# Pwr.net
KiCad netlist of a schematic drawn in Altium Designer
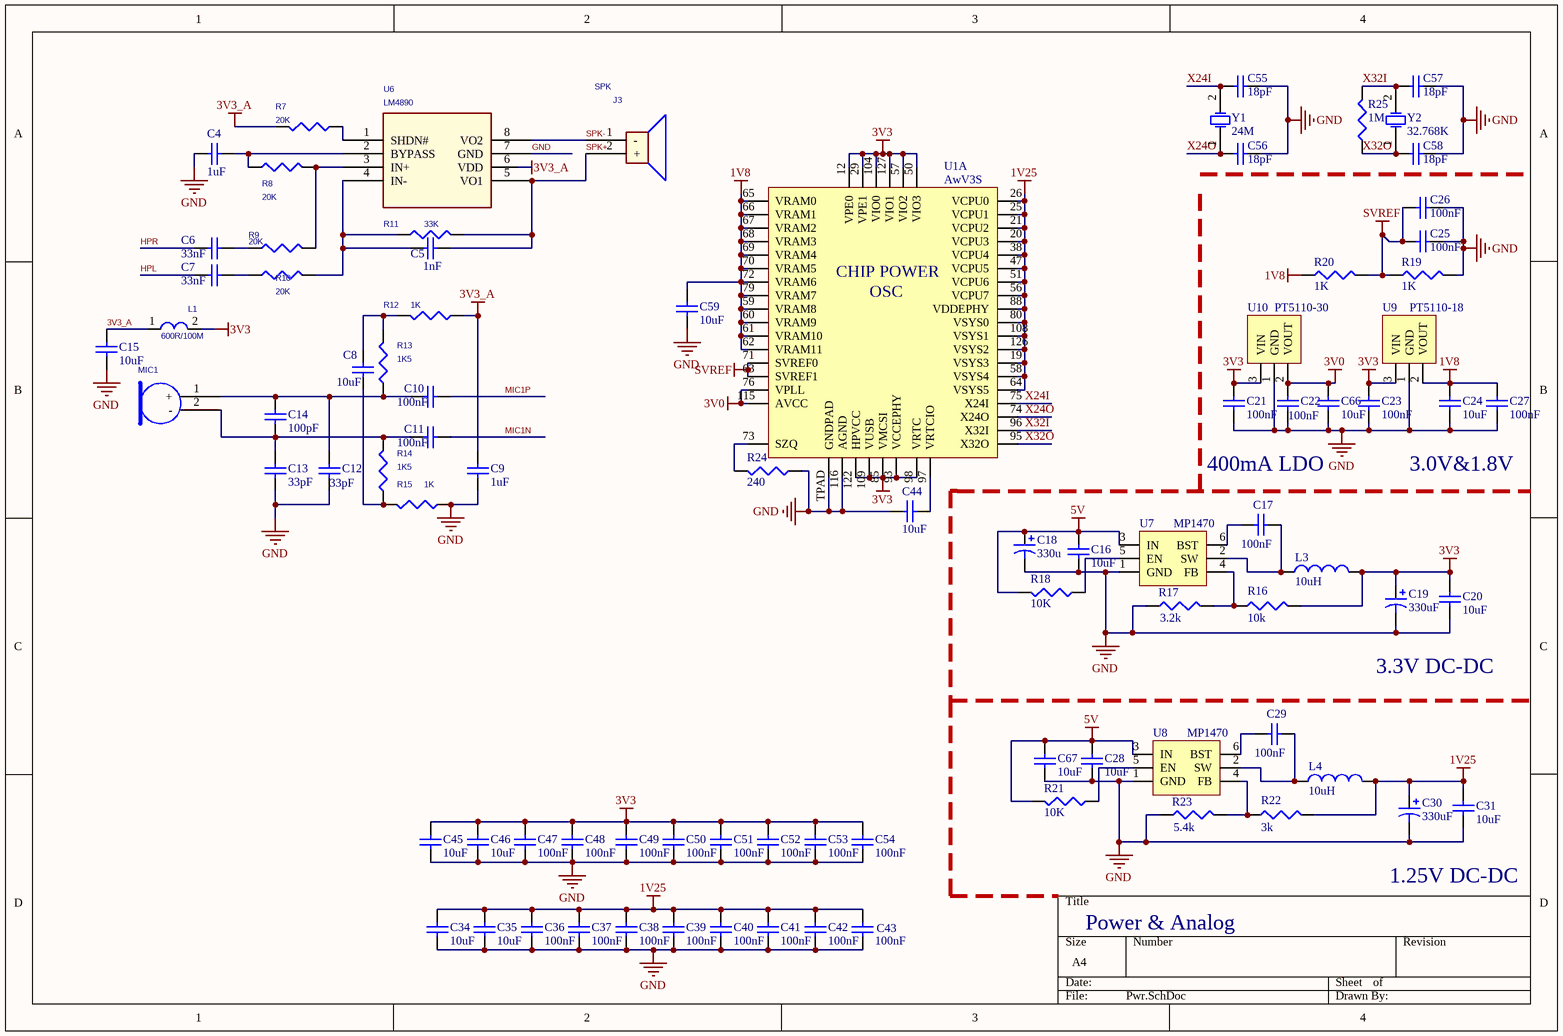
[diagram p0: Pwr.SchDoc]

(export (version "E")
  (design (tool "Eeschema 10.0.6"))
  (components
    (comp (ref "C4")
      (value "1uF")
      (footprint "0603C")
      (description "Capacitor")
      (fields (field (name "Comment") "105") (field (name "PUBLISHER") "Altium Limited"))
      (libsource (lib "Miscellaneous Devices") (part "Cap"))
    )
    (comp (ref "C5")
      (value "1nF")
      (footprint "0603C")
      (description "Capacitor")
      (fields (field (name "Comment") "102") (field (name "PUBLISHER") "Altium Limited"))
      (libsource (lib "Miscellaneous Devices") (part "Cap"))
    )
    (comp (ref "C6")
      (value "33nF")
      (footprint "0603C")
      (description "Capacitor")
      (fields (field (name "Comment") "333") (field (name "PUBLISHER") "Altium Limited"))
      (libsource (lib "Miscellaneous Devices") (part "Cap"))
    )
    (comp (ref "C7")
      (value "33nF")
      (footprint "0603C")
      (description "Capacitor")
      (fields (field (name "Comment") "333") (field (name "PUBLISHER") "Altium Limited"))
      (libsource (lib "Miscellaneous Devices") (part "Cap"))
    )
    (comp (ref "C8")
      (value "10uF")
      (footprint "0603C")
      (description "Capacitor")
      (fields (field (name "Comment") "105") (field (name "PUBLISHER") "Altium Limited"))
      (libsource (lib "Miscellaneous Devices") (part "Cap"))
    )
    (comp (ref "C9")
      (value "1uF")
      (footprint "0603C")
      (description "Capacitor")
      (fields (field (name "Comment") "105") (field (name "PUBLISHER") "Altium Limited"))
      (libsource (lib "Miscellaneous Devices") (part "Cap"))
    )
    (comp (ref "C10")
      (value "100nF")
      (footprint "0603C")
      (description "Capacitor")
      (fields (field (name "Comment") "104") (field (name "PUBLISHER") "Altium Limited"))
      (libsource (lib "Miscellaneous Devices") (part "Cap"))
    )
    (comp (ref "C11")
      (value "100nF")
      (footprint "0603C")
      (description "Capacitor")
      (fields (field (name "Comment") "104") (field (name "PUBLISHER") "Altium Limited"))
      (libsource (lib "Miscellaneous Devices") (part "Cap"))
    )
    (comp (ref "C12")
      (value "33pF")
      (footprint "0603C")
      (description "Capacitor")
      (fields (field (name "Comment") "333") (field (name "PUBLISHER") "Altium Limited"))
      (libsource (lib "Miscellaneous Devices") (part "Cap"))
    )
    (comp (ref "C13")
      (value "33pF")
      (footprint "0603C")
      (description "Capacitor")
      (fields (field (name "Comment") "333") (field (name "PUBLISHER") "Altium Limited"))
      (libsource (lib "Miscellaneous Devices") (part "Cap"))
    )
    (comp (ref "C14")
      (value "100pF")
      (footprint "0603C")
      (description "Capacitor")
      (fields (field (name "Comment") "101") (field (name "PUBLISHER") "Altium Limited"))
      (libsource (lib "Miscellaneous Devices") (part "Cap"))
    )
    (comp (ref "C15")
      (value "10uF")
      (footprint "0603C")
      (description "Capacitor")
      (fields (field (name "Comment") "Cap") (field (name "PUBLISHER") "Altium Limited"))
      (libsource (lib "Miscellaneous Devices") (part "Cap"))
    )
    (comp (ref "C16")
      (value "10uF")
      (footprint "0805-0C")
      (description "Ceramic Capacitor 0603")
      (fields (field (name "Comment") "106") (field (name "PUBLISHER") "Altium Limited"))
      (libsource (lib "Miscellaneous Devices") (part "Cap"))
    )
    (comp (ref "C17")
      (value "100nF")
      (footprint "0603C")
      (description "Ceramic Capacitor 0603")
      (fields (field (name "Comment") "104") (field (name "PUBLISHER") "Altium Limited"))
      (libsource (lib "Miscellaneous Devices") (part "Cap"))
    )
    (comp (ref "C18")
      (value "330u")
      (footprint "TanCap-1210")
      (description "Polarized Capacitor (Radial)")
      (fields (field (name "PUBLISHER") "Altium Limited"))
      (libsource (lib "Miscellaneous Devices") (part "Cap Pol1"))
    )
    (comp (ref "C19")
      (value "330uF")
      (footprint "TanCap-1210")
      (description "Polarized Capacitor (Radial)")
      (fields (field (name "Comment") "330u") (field (name "PUBLISHER") "Altium Limited"))
      (libsource (lib "Miscellaneous Devices") (part "Cap Pol1"))
    )
    (comp (ref "C20")
      (value "10uF")
      (footprint "0805-0C")
      (description "Ceramic Capacitor 0603")
      (fields (field (name "Comment") "106") (field (name "PUBLISHER") "Altium Limited"))
      (libsource (lib "Miscellaneous Devices") (part "Cap"))
    )
    (comp (ref "C21")
      (value "100nF")
      (footprint "0603C")
      (description "Ceramic 0603 Capacitor")
      (fields (field (name "Comment") "104") (field (name "PUBLISHER") "Altium Limited"))
      (libsource (lib "Miscellaneous Devices") (part "Cap"))
    )
    (comp (ref "C22")
      (value "100nF")
      (footprint "0603C")
      (description "Ceramic 0603 Capacitor")
      (fields (field (name "Comment") "104") (field (name "PUBLISHER") "Altium Limited"))
      (libsource (lib "Miscellaneous Devices") (part "Cap"))
    )
    (comp (ref "C23")
      (value "100nF")
      (footprint "0603C")
      (description "Ceramic 0603 Capacitor")
      (fields (field (name "Comment") "104") (field (name "PUBLISHER") "Altium Limited"))
      (libsource (lib "Miscellaneous Devices") (part "Cap"))
    )
    (comp (ref "C24")
      (value "10uF")
      (footprint "0603C")
      (description "Ceramic 0603 Capacitor")
      (fields (field (name "Comment") "104") (field (name "PUBLISHER") "Altium Limited"))
      (libsource (lib "Miscellaneous Devices") (part "Cap"))
    )
    (comp (ref "C25")
      (value "100nF")
      (footprint "0603C")
      (description "Capacitor")
      (fields (field (name "Comment") "104") (field (name "PUBLISHER") "Altium Limited"))
      (libsource (lib "Miscellaneous Devices") (part "Cap"))
    )
    (comp (ref "C26")
      (value "100nF")
      (footprint "0603C")
      (description "Capacitor")
      (fields (field (name "Comment") "104") (field (name "PUBLISHER") "Altium Limited"))
      (libsource (lib "Miscellaneous Devices") (part "Cap"))
    )
    (comp (ref "C27")
      (value "100nF")
      (footprint "0603C")
      (description "Ceramic 0603 Capacitor")
      (fields (field (name "Comment") "106") (field (name "PUBLISHER") "Altium Limited"))
      (libsource (lib "Miscellaneous Devices") (part "Cap"))
    )
    (comp (ref "C28")
      (value "10uF")
      (footprint "0805-0C")
      (description "Ceramic Capacitor 0603")
      (fields (field (name "Comment") "106") (field (name "PUBLISHER") "Altium Limited"))
      (libsource (lib "Miscellaneous Devices") (part "Cap"))
    )
    (comp (ref "C29")
      (value "100nF")
      (footprint "0603C")
      (description "Ceramic Capacitor 0603")
      (fields (field (name "Comment") "104") (field (name "PUBLISHER") "Altium Limited"))
      (libsource (lib "Miscellaneous Devices") (part "Cap"))
    )
    (comp (ref "C30")
      (value "330uF")
      (footprint "TanCap-1210")
      (description "Polarized Capacitor (Radial)")
      (fields (field (name "Comment") "330u") (field (name "PUBLISHER") "Altium Limited"))
      (libsource (lib "Miscellaneous Devices") (part "Cap Pol1"))
    )
    (comp (ref "C31")
      (value "10uF")
      (footprint "0805-0C")
      (description "Ceramic Capacitor 0603")
      (fields (field (name "Comment") "106") (field (name "PUBLISHER") "Altium Limited"))
      (libsource (lib "Miscellaneous Devices") (part "Cap"))
    )
    (comp (ref "C34")
      (value "10uF")
      (footprint "0603C")
      (description "Capacitor")
      (fields (field (name "Comment") "106") (field (name "PUBLISHER") "Altium Limited"))
      (libsource (lib "Miscellaneous Devices") (part "Cap"))
    )
    (comp (ref "C35")
      (value "10uF")
      (footprint "0603C")
      (description "Capacitor")
      (fields (field (name "Comment") "106") (field (name "PUBLISHER") "Altium Limited"))
      (libsource (lib "Miscellaneous Devices") (part "Cap"))
    )
    (comp (ref "C36")
      (value "100nF")
      (footprint "0603C")
      (description "Capacitor")
      (fields (field (name "Comment") "Cap") (field (name "PUBLISHER") "Altium Limited"))
      (libsource (lib "Miscellaneous Devices") (part "Cap"))
    )
    (comp (ref "C37")
      (value "100nF")
      (footprint "0603C")
      (description "Capacitor")
      (fields (field (name "Comment") "Cap") (field (name "PUBLISHER") "Altium Limited"))
      (libsource (lib "Miscellaneous Devices") (part "Cap"))
    )
    (comp (ref "C38")
      (value "100nF")
      (footprint "0603C")
      (description "Capacitor")
      (fields (field (name "Comment") "Cap") (field (name "PUBLISHER") "Altium Limited"))
      (libsource (lib "Miscellaneous Devices") (part "Cap"))
    )
    (comp (ref "C39")
      (value "100nF")
      (footprint "0603C")
      (description "Capacitor")
      (fields (field (name "Comment") "Cap") (field (name "PUBLISHER") "Altium Limited"))
      (libsource (lib "Miscellaneous Devices") (part "Cap"))
    )
    (comp (ref "C40")
      (value "100nF")
      (footprint "0603C")
      (description "Capacitor")
      (fields (field (name "Comment") "Cap") (field (name "PUBLISHER") "Altium Limited"))
      (libsource (lib "Miscellaneous Devices") (part "Cap"))
    )
    (comp (ref "C41")
      (value "100nF")
      (footprint "0603C")
      (description "Capacitor")
      (fields (field (name "Comment") "Cap") (field (name "PUBLISHER") "Altium Limited"))
      (libsource (lib "Miscellaneous Devices") (part "Cap"))
    )
    (comp (ref "C42")
      (value "100nF")
      (footprint "0603C")
      (description "Capacitor")
      (fields (field (name "Comment") "Cap") (field (name "PUBLISHER") "Altium Limited"))
      (libsource (lib "Miscellaneous Devices") (part "Cap"))
    )
    (comp (ref "C43")
      (value "100nF")
      (footprint "0603C")
      (description "Capacitor")
      (fields (field (name "Comment") "Cap") (field (name "PUBLISHER") "Altium Limited"))
      (libsource (lib "Miscellaneous Devices") (part "Cap"))
    )
    (comp (ref "C44")
      (value "10uF")
      (footprint "0603C")
      (description "Capacitor")
      (fields (field (name "Comment") "106") (field (name "PUBLISHER") "Altium Limited"))
      (libsource (lib "Miscellaneous Devices") (part "Cap"))
    )
    (comp (ref "C45")
      (value "10uF")
      (footprint "0603C")
      (description "Capacitor")
      (fields (field (name "Comment") "106") (field (name "PUBLISHER") "Altium Limited"))
      (libsource (lib "Miscellaneous Devices") (part "Cap"))
    )
    (comp (ref "C46")
      (value "10uF")
      (footprint "0603C")
      (description "Capacitor")
      (fields (field (name "Comment") "106") (field (name "PUBLISHER") "Altium Limited"))
      (libsource (lib "Miscellaneous Devices") (part "Cap"))
    )
    (comp (ref "C47")
      (value "100nF")
      (footprint "0603C")
      (description "Capacitor")
      (fields (field (name "Comment") "Cap") (field (name "PUBLISHER") "Altium Limited"))
      (libsource (lib "Miscellaneous Devices") (part "Cap"))
    )
    (comp (ref "C48")
      (value "100nF")
      (footprint "0603C")
      (description "Capacitor")
      (fields (field (name "Comment") "Cap") (field (name "PUBLISHER") "Altium Limited"))
      (libsource (lib "Miscellaneous Devices") (part "Cap"))
    )
    (comp (ref "C49")
      (value "100nF")
      (footprint "0603C")
      (description "Capacitor")
      (fields (field (name "Comment") "Cap") (field (name "PUBLISHER") "Altium Limited"))
      (libsource (lib "Miscellaneous Devices") (part "Cap"))
    )
    (comp (ref "C50")
      (value "100nF")
      (footprint "0603C")
      (description "Capacitor")
      (fields (field (name "Comment") "Cap") (field (name "PUBLISHER") "Altium Limited"))
      (libsource (lib "Miscellaneous Devices") (part "Cap"))
    )
    (comp (ref "C51")
      (value "100nF")
      (footprint "0603C")
      (description "Capacitor")
      (fields (field (name "Comment") "Cap") (field (name "PUBLISHER") "Altium Limited"))
      (libsource (lib "Miscellaneous Devices") (part "Cap"))
    )
    (comp (ref "C52")
      (value "100nF")
      (footprint "0603C")
      (description "Capacitor")
      (fields (field (name "Comment") "Cap") (field (name "PUBLISHER") "Altium Limited"))
      (libsource (lib "Miscellaneous Devices") (part "Cap"))
    )
    (comp (ref "C53")
      (value "100nF")
      (footprint "0603C")
      (description "Capacitor")
      (fields (field (name "Comment") "Cap") (field (name "PUBLISHER") "Altium Limited"))
      (libsource (lib "Miscellaneous Devices") (part "Cap"))
    )
    (comp (ref "C54")
      (value "100nF")
      (footprint "0603C")
      (description "Capacitor")
      (fields (field (name "Comment") "Cap") (field (name "PUBLISHER") "Altium Limited"))
      (libsource (lib "Miscellaneous Devices") (part "Cap"))
    )
    (comp (ref "C55")
      (value "18pF")
      (footprint "0603C")
      (description "Capacitor")
      (fields (field (name "Comment") "18P") (field (name "PUBLISHER") "Altium Limited"))
      (libsource (lib "Miscellaneous Devices") (part "Cap"))
    )
    (comp (ref "C56")
      (value "18pF")
      (footprint "0603C")
      (description "Capacitor")
      (fields (field (name "Comment") "18P") (field (name "PUBLISHER") "Altium Limited"))
      (libsource (lib "Miscellaneous Devices") (part "Cap"))
    )
    (comp (ref "C57")
      (value "18pF")
      (footprint "0603C")
      (description "Capacitor")
      (fields (field (name "Comment") "33P") (field (name "PUBLISHER") "Altium Limited"))
      (libsource (lib "Miscellaneous Devices") (part "Cap"))
    )
    (comp (ref "C58")
      (value "18pF")
      (footprint "0603C")
      (description "Capacitor")
      (fields (field (name "Comment") "33P") (field (name "PUBLISHER") "Altium Limited"))
      (libsource (lib "Miscellaneous Devices") (part "Cap"))
    )
    (comp (ref "C59")
      (value "10uF")
      (footprint "0603C")
      (description "Ceramic 0603 Capacitor")
      (fields (field (name "Comment") "106") (field (name "PUBLISHER") "Altium Limited"))
      (libsource (lib "Miscellaneous Devices") (part "Cap"))
    )
    (comp (ref "C66")
      (value "10uF")
      (footprint "0603C")
      (description "0603 Ceramic Capacitor")
      (fields (field (name "Comment") "106") (field (name "PUBLISHER") "Altium Limited"))
      (libsource (lib "Miscellaneous Devices") (part "Cap"))
    )
    (comp (ref "C67")
      (value "10uF")
      (footprint "0805-0C")
      (description "Ceramic Capacitor 0603")
      (fields (field (name "Comment") "106") (field (name "PUBLISHER") "Altium Limited"))
      (libsource (lib "Miscellaneous Devices") (part "Cap"))
    )
    (comp (ref "J3") (value "SPK") (footprint "HDR1X2") (libsource (lib "*") (part "SPEAKER")))
    (comp (ref "L1")
      (value "600R/100M")
      (footprint "L0603")
      (description "RoHS BEAD/600ohm 100Mhz Z=600Ω DCR<0.2Ω 800mA SMT L0603")
      (libsource (lib "*") (part "INDUCTOR_0_Dup1"))
    )
    (comp (ref "L3")
      (value "10uH")
      (footprint "PIND0650")
      (description "Inductor 0606")
      (fields (field (name "PUBLISHER") "Altium Limited"))
      (libsource (lib "Miscellaneous Devices") (part "Inductor"))
    )
    (comp (ref "L4")
      (value "10uH")
      (footprint "PIND0650")
      (description "Inductor 0606")
      (fields (field (name "Comment") "Inductor") (field (name "PUBLISHER") "Altium Limited"))
      (libsource (lib "Miscellaneous Devices") (part "Inductor"))
    )
    (comp (ref "MIC1") (value "Micphone") (footprint "mic_4015") (libsource (lib "*") (part "Micphone_0")))
    (comp (ref "R7") (value "20K") (footprint "0603R") (libsource (lib "*") (part "?_0")))
    (comp (ref "R8") (value "20K") (footprint "0603R") (libsource (lib "*") (part "?_0")))
    (comp (ref "R9") (value "20K") (footprint "0603R") (libsource (lib "*") (part "?_0")))
    (comp (ref "R10") (value "20K") (footprint "0603R") (libsource (lib "*") (part "?_0")))
    (comp (ref "R11") (value "33K") (footprint "0603R") (libsource (lib "*") (part "?_0")))
    (comp (ref "R12") (value "1K") (footprint "0603R") (libsource (lib "*") (part "R_Dup4")))
    (comp (ref "R13") (value "1K5") (footprint "0603R") (libsource (lib "*") (part "R_Dup4")))
    (comp (ref "R14") (value "1K5") (footprint "0603R") (libsource (lib "*") (part "R_Dup4")))
    (comp (ref "R15") (value "1K") (footprint "0603R") (libsource (lib "*") (part "R_Dup4")))
    (comp (ref "R16")
      (value "10k")
      (footprint "0603R")
      (description "Resistor")
      (fields (field (name "Comment") "10K") (field (name "PUBLISHER") "Altium Limited"))
      (libsource (lib "Miscellaneous Devices") (part "Res3"))
    )
    (comp (ref "R17")
      (value "3.2k")
      (footprint "0603R")
      (description "Resistor")
      (fields (field (name "Comment") "3K2") (field (name "PUBLISHER") "Altium Limited"))
      (libsource (lib "Miscellaneous Devices") (part "Res3"))
    )
    (comp (ref "R18")
      (value "10K")
      (footprint "0603R")
      (description "Resistor")
      (fields (field (name "PUBLISHER") "Altium Limited"))
      (libsource (lib "Miscellaneous Devices") (part "Res3"))
    )
    (comp (ref "R19")
      (value "1K")
      (footprint "0603R")
      (description "0603 Resistor")
      (fields (field (name "PUBLISHER") "Altium Limited"))
      (libsource (lib "Miscellaneous Devices") (part "Res3"))
    )
    (comp (ref "R20")
      (value "1K")
      (footprint "0603R")
      (description "0603 Resistor")
      (fields (field (name "PUBLISHER") "Altium Limited"))
      (libsource (lib "Miscellaneous Devices") (part "Res3"))
    )
    (comp (ref "R21")
      (value "10K")
      (footprint "0603R")
      (description "Resistor")
      (fields (field (name "PUBLISHER") "Altium Limited"))
      (libsource (lib "Miscellaneous Devices") (part "Res3"))
    )
    (comp (ref "R22")
      (value "3k")
      (footprint "0603R")
      (description "Resistor")
      (fields (field (name "Comment") "3K") (field (name "PUBLISHER") "Altium Limited"))
      (libsource (lib "Miscellaneous Devices") (part "Res3"))
    )
    (comp (ref "R23")
      (value "5.4k")
      (footprint "0603R")
      (description "Resistor")
      (fields (field (name "Comment") "5.4K") (field (name "PUBLISHER") "Altium Limited"))
      (libsource (lib "Miscellaneous Devices") (part "Res3"))
    )
    (comp (ref "R24")
      (value "240")
      (footprint "0603R")
      (description "Resistor")
      (fields (field (name "PUBLISHER") "Altium Limited"))
      (libsource (lib "Miscellaneous Devices") (part "Res3"))
    )
    (comp (ref "R25")
      (value "1M")
      (footprint "0603R")
      (description "Resistor")
      (fields (field (name "PUBLISHER") "Altium Limited"))
      (libsource (lib "Miscellaneous Devices") (part "Res3"))
    )
    (comp (ref "U1") (value "AwV3S") (libsource (lib "AwChips") (part "Aw_V3S")))
    (comp (ref "U6") (value "LM4890") (footprint "MSOP8") (libsource (lib "*") (part "LY8006_0")))
    (comp (ref "U7") (value "MP1470") (footprint "SOT23-6") (libsource (lib "PowerChips") (part "MP1470")))
    (comp (ref "U8") (value "MP1470") (footprint "SOT23-6") (libsource (lib "PowerChips") (part "MP1470")))
    (comp (ref "U9") (value "PT5110-18") (footprint "SOT-23") (libsource (lib "PowerChips") (part "PT5110")))
    (comp (ref "U10") (value "PT5110-30") (footprint "SOT-23") (libsource (lib "PowerChips") (part "PT5110")))
    (comp (ref "Y1")
      (value "24M")
      (footprint "XTAL-5032")
      (description "Crystal Oscillator")
      (fields (field (name "PUBLISHER") "Altium Limited"))
      (libsource (lib "Miscellaneous Devices") (part "XTAL"))
    )
    (comp (ref "Y2")
      (value "32.768K")
      (footprint "XTAL-3215")
      (description "Crystal Oscillator")
      (fields (field (name "PUBLISHER") "Altium Limited"))
      (libsource (lib "Miscellaneous Devices") (part "XTAL"))
    )
  )
  (nets
    (net (code "1") (name "/HPL") (class "Default")
      (node (ref "C7") (pin "2") (pinfunction "2_2") (pintype "passive"))
    )
    (net (code "2") (name "/HPR") (class "Default")
      (node (ref "C6") (pin "2") (pinfunction "2_2") (pintype "passive"))
    )
    (net (code "3") (name "/MIC1N") (class "Default")
      (node (ref "C11") (pin "1") (pinfunction "1_1") (pintype "passive"))
    )
    (net (code "4") (name "/MIC1P") (class "Default")
      (node (ref "C10") (pin "1") (pinfunction "1_1") (pintype "passive"))
    )
    (net (code "5") (name "/SPK+") (class "Default")
      (node (ref "C5") (pin "1") (pinfunction "1_1") (pintype "passive"))
      (node (ref "J3") (pin "2") (pinfunction "+_2") (pintype "passive"))
      (node (ref "R11") (pin "2") (pinfunction "2_2") (pintype "passive"))
      (node (ref "U6") (pin "5") (pinfunction "VO1_5") (pintype "passive"))
    )
    (net (code "6") (name "/SPK-") (class "Default")
      (node (ref "J3") (pin "1") (pinfunction "-_1") (pintype "passive"))
      (node (ref "U6") (pin "8") (pinfunction "VO2_8") (pintype "passive"))
    )
    (net (code "7") (name "/X24I") (class "Default")
      (node (ref "C55") (pin "1") (pinfunction "1_1") (pintype "passive"))
      (node (ref "U1") (pin "75") (pinfunction "X24I_75") (pintype "passive"))
      (node (ref "Y1") (pin "2") (pinfunction "OSC2_2") (pintype "passive"))
    )
    (net (code "8") (name "/X24O") (class "Default")
      (node (ref "C56") (pin "1") (pinfunction "1_1") (pintype "passive"))
      (node (ref "U1") (pin "74") (pinfunction "X24O_74") (pintype "passive"))
      (node (ref "Y1") (pin "1") (pinfunction "OSC1_1") (pintype "passive"))
    )
    (net (code "9") (name "/X32I") (class "Default")
      (node (ref "C57") (pin "1") (pinfunction "1_1") (pintype "passive"))
      (node (ref "R25") (pin "2") (pinfunction "2_2") (pintype "passive"))
      (node (ref "U1") (pin "96") (pinfunction "X32I_96") (pintype "passive"))
      (node (ref "Y2") (pin "2") (pinfunction "OSC2_2") (pintype "passive"))
    )
    (net (code "10") (name "/X32O") (class "Default")
      (node (ref "C58") (pin "1") (pinfunction "1_1") (pintype "passive"))
      (node (ref "R25") (pin "1") (pinfunction "1_1") (pintype "passive"))
      (node (ref "U1") (pin "95") (pinfunction "X32O_95") (pintype "passive"))
      (node (ref "Y2") (pin "1") (pinfunction "OSC1_1") (pintype "passive"))
    )
    (net (code "11") (name "1V8") (class "Default")
      (node (ref "C24") (pin "2") (pinfunction "2_2") (pintype "passive"))
      (node (ref "C27") (pin "2") (pinfunction "2_2") (pintype "passive"))
      (node (ref "C59") (pin "2") (pinfunction "2_2") (pintype "passive"))
      (node (ref "R20") (pin "1") (pinfunction "1_1") (pintype "passive"))
      (node (ref "U1") (pin "59") (pinfunction "VRAM8_59") (pintype "passive"))
      (node (ref "U1") (pin "60") (pinfunction "VRAM9_60") (pintype "passive"))
      (node (ref "U1") (pin "61") (pinfunction "VRAM10_61") (pintype "passive"))
      (node (ref "U1") (pin "62") (pinfunction "VRAM11_62") (pintype "passive"))
      (node (ref "U1") (pin "65") (pinfunction "VRAM0_65") (pintype "passive"))
      (node (ref "U1") (pin "66") (pinfunction "VRAM1_66") (pintype "passive"))
      (node (ref "U1") (pin "67") (pinfunction "VRAM2_67") (pintype "passive"))
      (node (ref "U1") (pin "68") (pinfunction "VRAM3_68") (pintype "passive"))
      (node (ref "U1") (pin "69") (pinfunction "VRAM4_69") (pintype "passive"))
      (node (ref "U1") (pin "70") (pinfunction "VRAM5_70") (pintype "passive"))
      (node (ref "U1") (pin "72") (pinfunction "VRAM6_72") (pintype "power_in"))
      (node (ref "U1") (pin "79") (pinfunction "VRAM7_79") (pintype "passive"))
      (node (ref "U9") (pin "2") (pinfunction "VOUT_2") (pintype "power_in"))
    )
    (net (code "12") (name "1V25") (class "Default")
      (node (ref "C30") (pin "1") (pinfunction "1_1") (pintype "passive"))
      (node (ref "C31") (pin "2") (pinfunction "2_2") (pintype "passive"))
      (node (ref "C34") (pin "2") (pinfunction "2_2") (pintype "passive"))
      (node (ref "C35") (pin "2") (pinfunction "2_2") (pintype "passive"))
      (node (ref "C36") (pin "2") (pinfunction "2_2") (pintype "passive"))
      (node (ref "C37") (pin "2") (pinfunction "2_2") (pintype "passive"))
      (node (ref "C38") (pin "2") (pinfunction "2_2") (pintype "passive"))
      (node (ref "C39") (pin "2") (pinfunction "2_2") (pintype "passive"))
      (node (ref "C40") (pin "2") (pinfunction "2_2") (pintype "passive"))
      (node (ref "C41") (pin "2") (pinfunction "2_2") (pintype "passive"))
      (node (ref "C42") (pin "2") (pinfunction "2_2") (pintype "passive"))
      (node (ref "C43") (pin "2") (pinfunction "2_2") (pintype "passive"))
      (node (ref "L4") (pin "2") (pinfunction "2_2") (pintype "passive"))
      (node (ref "R22") (pin "2") (pinfunction "2_2") (pintype "passive"))
      (node (ref "U1") (pin "108") (pinfunction "VSYS1_108") (pintype "passive"))
      (node (ref "U1") (pin "126") (pinfunction "VSYS2_126") (pintype "passive"))
      (node (ref "U1") (pin "19") (pinfunction "VSYS3_19") (pintype "passive"))
      (node (ref "U1") (pin "20") (pinfunction "VCPU3_20") (pintype "passive"))
      (node (ref "U1") (pin "21") (pinfunction "VCPU2_21") (pintype "passive"))
      (node (ref "U1") (pin "25") (pinfunction "VCPU1_25") (pintype "passive"))
      (node (ref "U1") (pin "26") (pinfunction "VCPU0_26") (pintype "passive"))
      (node (ref "U1") (pin "38") (pinfunction "VCPU4_38") (pintype "passive"))
      (node (ref "U1") (pin "47") (pinfunction "VCPU5_47") (pintype "passive"))
      (node (ref "U1") (pin "51") (pinfunction "VCPU6_51") (pintype "passive"))
      (node (ref "U1") (pin "56") (pinfunction "VCPU7_56") (pintype "passive"))
      (node (ref "U1") (pin "58") (pinfunction "VSYS4_58") (pintype "passive"))
      (node (ref "U1") (pin "64") (pinfunction "VSYS5_64") (pintype "passive"))
      (node (ref "U1") (pin "80") (pinfunction "VSYS0_80") (pintype "passive"))
      (node (ref "U1") (pin "88") (pinfunction "VDDEPHY_88") (pintype "passive"))
    )
    (net (code "13") (name "3V0") (class "Default")
      (node (ref "C22") (pin "2") (pinfunction "2_2") (pintype "passive"))
      (node (ref "C66") (pin "1") (pinfunction "1_1") (pintype "passive"))
      (node (ref "U1") (pin "115") (pinfunction "AVCC_115") (pintype "passive"))
      (node (ref "U1") (pin "76") (pinfunction "VPLL_76") (pintype "passive"))
      (node (ref "U10") (pin "2") (pinfunction "VOUT_2") (pintype "power_in"))
    )
    (net (code "14") (name "3V3") (class "Default")
      (node (ref "C19") (pin "1") (pinfunction "1_1") (pintype "passive"))
      (node (ref "C20") (pin "2") (pinfunction "2_2") (pintype "passive"))
      (node (ref "C21") (pin "2") (pinfunction "2_2") (pintype "passive"))
      (node (ref "C23") (pin "2") (pinfunction "2_2") (pintype "passive"))
      (node (ref "C45") (pin "2") (pinfunction "2_2") (pintype "passive"))
      (node (ref "C46") (pin "2") (pinfunction "2_2") (pintype "passive"))
      (node (ref "C47") (pin "2") (pinfunction "2_2") (pintype "passive"))
      (node (ref "C48") (pin "2") (pinfunction "2_2") (pintype "passive"))
      (node (ref "C49") (pin "2") (pinfunction "2_2") (pintype "passive"))
      (node (ref "C50") (pin "2") (pinfunction "2_2") (pintype "passive"))
      (node (ref "C51") (pin "2") (pinfunction "2_2") (pintype "passive"))
      (node (ref "C52") (pin "2") (pinfunction "2_2") (pintype "passive"))
      (node (ref "C53") (pin "2") (pinfunction "2_2") (pintype "passive"))
      (node (ref "C54") (pin "2") (pinfunction "2_2") (pintype "passive"))
      (node (ref "L1") (pin "2") (pinfunction "2_2") (pintype "passive"))
      (node (ref "L3") (pin "2") (pinfunction "2_2") (pintype "passive"))
      (node (ref "R16") (pin "2") (pinfunction "2_2") (pintype "passive"))
      (node (ref "U1") (pin "104") (pinfunction "VIO0_104") (pintype "passive"))
      (node (ref "U1") (pin "109") (pinfunction "VUSB_109") (pintype "passive"))
      (node (ref "U1") (pin "12") (pinfunction "VPE0_12") (pintype "passive"))
      (node (ref "U1") (pin "122") (pinfunction "HPVCC_122") (pintype "passive"))
      (node (ref "U1") (pin "127") (pinfunction "VIO1_127") (pintype "passive"))
      (node (ref "U1") (pin "29") (pinfunction "VPE1_29") (pintype "passive"))
      (node (ref "U1") (pin "50") (pinfunction "VIO3_50") (pintype "passive"))
      (node (ref "U1") (pin "57") (pinfunction "VIO2_57") (pintype "passive"))
      (node (ref "U1") (pin "85") (pinfunction "VMCSI_85") (pintype "passive"))
      (node (ref "U1") (pin "93") (pinfunction "VCCEPHY_93") (pintype "passive"))
      (node (ref "U1") (pin "98") (pinfunction "VRTC_98") (pintype "passive"))
      (node (ref "U10") (pin "3") (pinfunction "VIN_3") (pintype "power_in"))
      (node (ref "U9") (pin "3") (pinfunction "VIN_3") (pintype "power_in"))
    )
    (net (code "15") (name "3V3_A") (class "Default")
      (node (ref "C15") (pin "2") (pinfunction "2_2") (pintype "passive"))
      (node (ref "C9") (pin "2") (pinfunction "2_2") (pintype "passive"))
      (node (ref "L1") (pin "1") (pinfunction "1_1") (pintype "passive"))
      (node (ref "R12") (pin "1") (pinfunction "1_1") (pintype "passive"))
      (node (ref "R7") (pin "2") (pinfunction "2_2") (pintype "passive"))
      (node (ref "U6") (pin "6") (pinfunction "VDD_6") (pintype "passive"))
    )
    (net (code "16") (name "5V") (class "Default")
      (node (ref "C16") (pin "2") (pinfunction "2_2") (pintype "passive"))
      (node (ref "C18") (pin "1") (pinfunction "1_1") (pintype "passive"))
      (node (ref "C28") (pin "2") (pinfunction "2_2") (pintype "passive"))
      (node (ref "C67") (pin "2") (pinfunction "2_2") (pintype "passive"))
      (node (ref "R18") (pin "2") (pinfunction "2_2") (pintype "passive"))
      (node (ref "R21") (pin "2") (pinfunction "2_2") (pintype "passive"))
      (node (ref "U7") (pin "3") (pinfunction "IN_3") (pintype "power_in"))
      (node (ref "U8") (pin "3") (pinfunction "IN_3") (pintype "power_in"))
    )
    (net (code "17") (name "GND") (class "Default")
      (node (ref "C12") (pin "1") (pinfunction "1_1") (pintype "passive"))
      (node (ref "C13") (pin "1") (pinfunction "1_1") (pintype "passive"))
      (node (ref "C15") (pin "1") (pinfunction "1_1") (pintype "passive"))
      (node (ref "C16") (pin "1") (pinfunction "1_1") (pintype "passive"))
      (node (ref "C18") (pin "2") (pinfunction "2_2") (pintype "passive"))
      (node (ref "C19") (pin "2") (pinfunction "2_2") (pintype "passive"))
      (node (ref "C20") (pin "1") (pinfunction "1_1") (pintype "passive"))
      (node (ref "C21") (pin "1") (pinfunction "1_1") (pintype "passive"))
      (node (ref "C22") (pin "1") (pinfunction "1_1") (pintype "passive"))
      (node (ref "C23") (pin "1") (pinfunction "1_1") (pintype "passive"))
      (node (ref "C24") (pin "1") (pinfunction "1_1") (pintype "passive"))
      (node (ref "C25") (pin "2") (pinfunction "2_2") (pintype "passive"))
      (node (ref "C26") (pin "2") (pinfunction "2_2") (pintype "passive"))
      (node (ref "C27") (pin "1") (pinfunction "1_1") (pintype "passive"))
      (node (ref "C28") (pin "1") (pinfunction "1_1") (pintype "passive"))
      (node (ref "C30") (pin "2") (pinfunction "2_2") (pintype "passive"))
      (node (ref "C31") (pin "1") (pinfunction "1_1") (pintype "passive"))
      (node (ref "C34") (pin "1") (pinfunction "1_1") (pintype "passive"))
      (node (ref "C35") (pin "1") (pinfunction "1_1") (pintype "passive"))
      (node (ref "C36") (pin "1") (pinfunction "1_1") (pintype "passive"))
      (node (ref "C37") (pin "1") (pinfunction "1_1") (pintype "passive"))
      (node (ref "C38") (pin "1") (pinfunction "1_1") (pintype "passive"))
      (node (ref "C39") (pin "1") (pinfunction "1_1") (pintype "passive"))
      (node (ref "C4") (pin "2") (pinfunction "2_2") (pintype "passive"))
      (node (ref "C40") (pin "1") (pinfunction "1_1") (pintype "passive"))
      (node (ref "C41") (pin "1") (pinfunction "1_1") (pintype "passive"))
      (node (ref "C42") (pin "1") (pinfunction "1_1") (pintype "passive"))
      (node (ref "C43") (pin "1") (pinfunction "1_1") (pintype "passive"))
      (node (ref "C44") (pin "1") (pinfunction "1_1") (pintype "passive"))
      (node (ref "C45") (pin "1") (pinfunction "1_1") (pintype "passive"))
      (node (ref "C46") (pin "1") (pinfunction "1_1") (pintype "passive"))
      (node (ref "C47") (pin "1") (pinfunction "1_1") (pintype "passive"))
      (node (ref "C48") (pin "1") (pinfunction "1_1") (pintype "passive"))
      (node (ref "C49") (pin "1") (pinfunction "1_1") (pintype "passive"))
      (node (ref "C50") (pin "1") (pinfunction "1_1") (pintype "passive"))
      (node (ref "C51") (pin "1") (pinfunction "1_1") (pintype "passive"))
      (node (ref "C52") (pin "1") (pinfunction "1_1") (pintype "passive"))
      (node (ref "C53") (pin "1") (pinfunction "1_1") (pintype "passive"))
      (node (ref "C54") (pin "1") (pinfunction "1_1") (pintype "passive"))
      (node (ref "C55") (pin "2") (pinfunction "2_2") (pintype "passive"))
      (node (ref "C56") (pin "2") (pinfunction "2_2") (pintype "passive"))
      (node (ref "C57") (pin "2") (pinfunction "2_2") (pintype "passive"))
      (node (ref "C58") (pin "2") (pinfunction "2_2") (pintype "passive"))
      (node (ref "C59") (pin "1") (pinfunction "1_1") (pintype "passive"))
      (node (ref "C66") (pin "2") (pinfunction "2_2") (pintype "passive"))
      (node (ref "C67") (pin "1") (pinfunction "1_1") (pintype "passive"))
      (node (ref "C9") (pin "1") (pinfunction "1_1") (pintype "passive"))
      (node (ref "R15") (pin "1") (pinfunction "1_1") (pintype "passive"))
      (node (ref "R17") (pin "1") (pinfunction "1_1") (pintype "passive"))
      (node (ref "R19") (pin "2") (pinfunction "2_2") (pintype "passive"))
      (node (ref "R23") (pin "1") (pinfunction "1_1") (pintype "passive"))
      (node (ref "R24") (pin "1") (pinfunction "1_1") (pintype "passive"))
      (node (ref "U1") (pin "116") (pinfunction "AGND_116") (pintype "passive"))
      (node (ref "U1") (pin "TPAD") (pinfunction "GNDPAD_TPAD") (pintype "power_in"))
      (node (ref "U10") (pin "1") (pinfunction "GND_1") (pintype "power_in"))
      (node (ref "U6") (pin "7") (pinfunction "GND_7") (pintype "passive"))
      (node (ref "U7") (pin "1") (pinfunction "GND_1") (pintype "power_in"))
      (node (ref "U8") (pin "1") (pinfunction "GND_1") (pintype "power_in"))
      (node (ref "U9") (pin "1") (pinfunction "GND_1") (pintype "power_in"))
    )
    (net (code "18") (name "Net-(C6-Pad1)") (class "Default")
      (node (ref "C6") (pin "1") (pinfunction "1_1") (pintype "passive"))
      (node (ref "R9") (pin "1") (pinfunction "1_1") (pintype "passive"))
    )
    (net (code "19") (name "Net-(C7-Pad1)") (class "Default")
      (node (ref "C7") (pin "1") (pinfunction "1_1") (pintype "passive"))
      (node (ref "R10") (pin "1") (pinfunction "1_1") (pintype "passive"))
    )
    (net (code "20") (name "Net-(C8-Pad1)") (class "Default")
      (node (ref "C8") (pin "1") (pinfunction "1_1") (pintype "passive"))
      (node (ref "R14") (pin "1") (pinfunction "1_1") (pintype "passive"))
      (node (ref "R15") (pin "2") (pinfunction "2_2") (pintype "passive"))
    )
    (net (code "21") (name "Net-(C8-Pad2)") (class "Default")
      (node (ref "C8") (pin "2") (pinfunction "2_2") (pintype "passive"))
      (node (ref "R12") (pin "2") (pinfunction "2_2") (pintype "passive"))
      (node (ref "R13") (pin "2") (pinfunction "2_2") (pintype "passive"))
    )
    (net (code "22") (name "Net-(MIC1-+)") (class "Default")
      (node (ref "C10") (pin "2") (pinfunction "2_2") (pintype "passive"))
      (node (ref "C12") (pin "2") (pinfunction "2_2") (pintype "passive"))
      (node (ref "C14") (pin "2") (pinfunction "2_2") (pintype "passive"))
      (node (ref "MIC1") (pin "1") (pinfunction "+_1") (pintype "passive"))
      (node (ref "R13") (pin "1") (pinfunction "1_1") (pintype "passive"))
    )
    (net (code "23") (name "Net-(MIC1--)") (class "Default")
      (node (ref "C11") (pin "2") (pinfunction "2_2") (pintype "passive"))
      (node (ref "C13") (pin "2") (pinfunction "2_2") (pintype "passive"))
      (node (ref "C14") (pin "1") (pinfunction "1_1") (pintype "passive"))
      (node (ref "MIC1") (pin "2") (pinfunction "-_2") (pintype "passive"))
      (node (ref "R14") (pin "2") (pinfunction "2_2") (pintype "passive"))
    )
    (net (code "24") (name "Net-(U1A-SZQ)") (class "Default")
      (node (ref "R24") (pin "2") (pinfunction "2_2") (pintype "passive"))
      (node (ref "U1") (pin "73") (pinfunction "SZQ_73") (pintype "passive"))
    )
    (net (code "25") (name "Net-(U1A-VRTCIO)") (class "Default")
      (node (ref "C44") (pin "2") (pinfunction "2_2") (pintype "passive"))
      (node (ref "U1") (pin "97") (pinfunction "VRTCIO_97") (pintype "passive"))
    )
    (net (code "26") (name "Net-(U6-BYPASS)") (class "Default")
      (node (ref "C4") (pin "1") (pinfunction "1_1") (pintype "passive"))
      (node (ref "R8") (pin "1") (pinfunction "1_1") (pintype "passive"))
      (node (ref "U6") (pin "2") (pinfunction "BYPASS_2") (pintype "passive"))
    )
    (net (code "27") (name "Net-(U6-IN+)") (class "Default")
      (node (ref "R8") (pin "2") (pinfunction "2_2") (pintype "passive"))
      (node (ref "R9") (pin "2") (pinfunction "2_2") (pintype "passive"))
      (node (ref "U6") (pin "3") (pinfunction "IN+_3") (pintype "passive"))
    )
    (net (code "28") (name "Net-(U6-IN-)") (class "Default")
      (node (ref "C5") (pin "2") (pinfunction "2_2") (pintype "passive"))
      (node (ref "R10") (pin "2") (pinfunction "2_2") (pintype "passive"))
      (node (ref "R11") (pin "1") (pinfunction "1_1") (pintype "passive"))
      (node (ref "U6") (pin "4") (pinfunction "IN-_4") (pintype "passive"))
    )
    (net (code "29") (name "Net-(U6-SHDN#)") (class "Default")
      (node (ref "R7") (pin "1") (pinfunction "1_1") (pintype "passive"))
      (node (ref "U6") (pin "1") (pinfunction "SHDN#_1") (pintype "passive"))
    )
    (net (code "30") (name "Net-(U7-BST)") (class "Default")
      (node (ref "C17") (pin "2") (pinfunction "2_2") (pintype "passive"))
      (node (ref "U7") (pin "6") (pinfunction "BST_6") (pintype "power_in"))
    )
    (net (code "31") (name "Net-(U7-EN)") (class "Default")
      (node (ref "R18") (pin "1") (pinfunction "1_1") (pintype "passive"))
      (node (ref "U7") (pin "5") (pinfunction "EN_5") (pintype "power_in"))
    )
    (net (code "32") (name "Net-(U7-FB)") (class "Default")
      (node (ref "R16") (pin "1") (pinfunction "1_1") (pintype "passive"))
      (node (ref "R17") (pin "2") (pinfunction "2_2") (pintype "passive"))
      (node (ref "U7") (pin "4") (pinfunction "FB_4") (pintype "power_in"))
    )
    (net (code "33") (name "Net-(U7-SW)") (class "Default")
      (node (ref "C17") (pin "1") (pinfunction "1_1") (pintype "passive"))
      (node (ref "L3") (pin "1") (pinfunction "1_1") (pintype "passive"))
      (node (ref "U7") (pin "2") (pinfunction "SW_2") (pintype "power_in"))
    )
    (net (code "34") (name "Net-(U8-BST)") (class "Default")
      (node (ref "C29") (pin "2") (pinfunction "2_2") (pintype "passive"))
      (node (ref "U8") (pin "6") (pinfunction "BST_6") (pintype "power_in"))
    )
    (net (code "35") (name "Net-(U8-EN)") (class "Default")
      (node (ref "R21") (pin "1") (pinfunction "1_1") (pintype "passive"))
      (node (ref "U8") (pin "5") (pinfunction "EN_5") (pintype "power_in"))
    )
    (net (code "36") (name "Net-(U8-FB)") (class "Default")
      (node (ref "R22") (pin "1") (pinfunction "1_1") (pintype "passive"))
      (node (ref "R23") (pin "2") (pinfunction "2_2") (pintype "passive"))
      (node (ref "U8") (pin "4") (pinfunction "FB_4") (pintype "power_in"))
    )
    (net (code "37") (name "Net-(U8-SW)") (class "Default")
      (node (ref "C29") (pin "1") (pinfunction "1_1") (pintype "passive"))
      (node (ref "L4") (pin "1") (pinfunction "1_1") (pintype "passive"))
      (node (ref "U8") (pin "2") (pinfunction "SW_2") (pintype "power_in"))
    )
    (net (code "38") (name "SVREF") (class "Default")
      (node (ref "C25") (pin "1") (pinfunction "1_1") (pintype "passive"))
      (node (ref "C26") (pin "1") (pinfunction "1_1") (pintype "passive"))
      (node (ref "R19") (pin "1") (pinfunction "1_1") (pintype "passive"))
      (node (ref "R20") (pin "2") (pinfunction "2_2") (pintype "passive"))
      (node (ref "U1") (pin "63") (pinfunction "SVREF1_63") (pintype "passive"))
      (node (ref "U1") (pin "71") (pinfunction "SVREF0_71") (pintype "passive"))
    )
  )
)
